# Bread.net
KiCad netlist of a schematic drawn in EAGLE
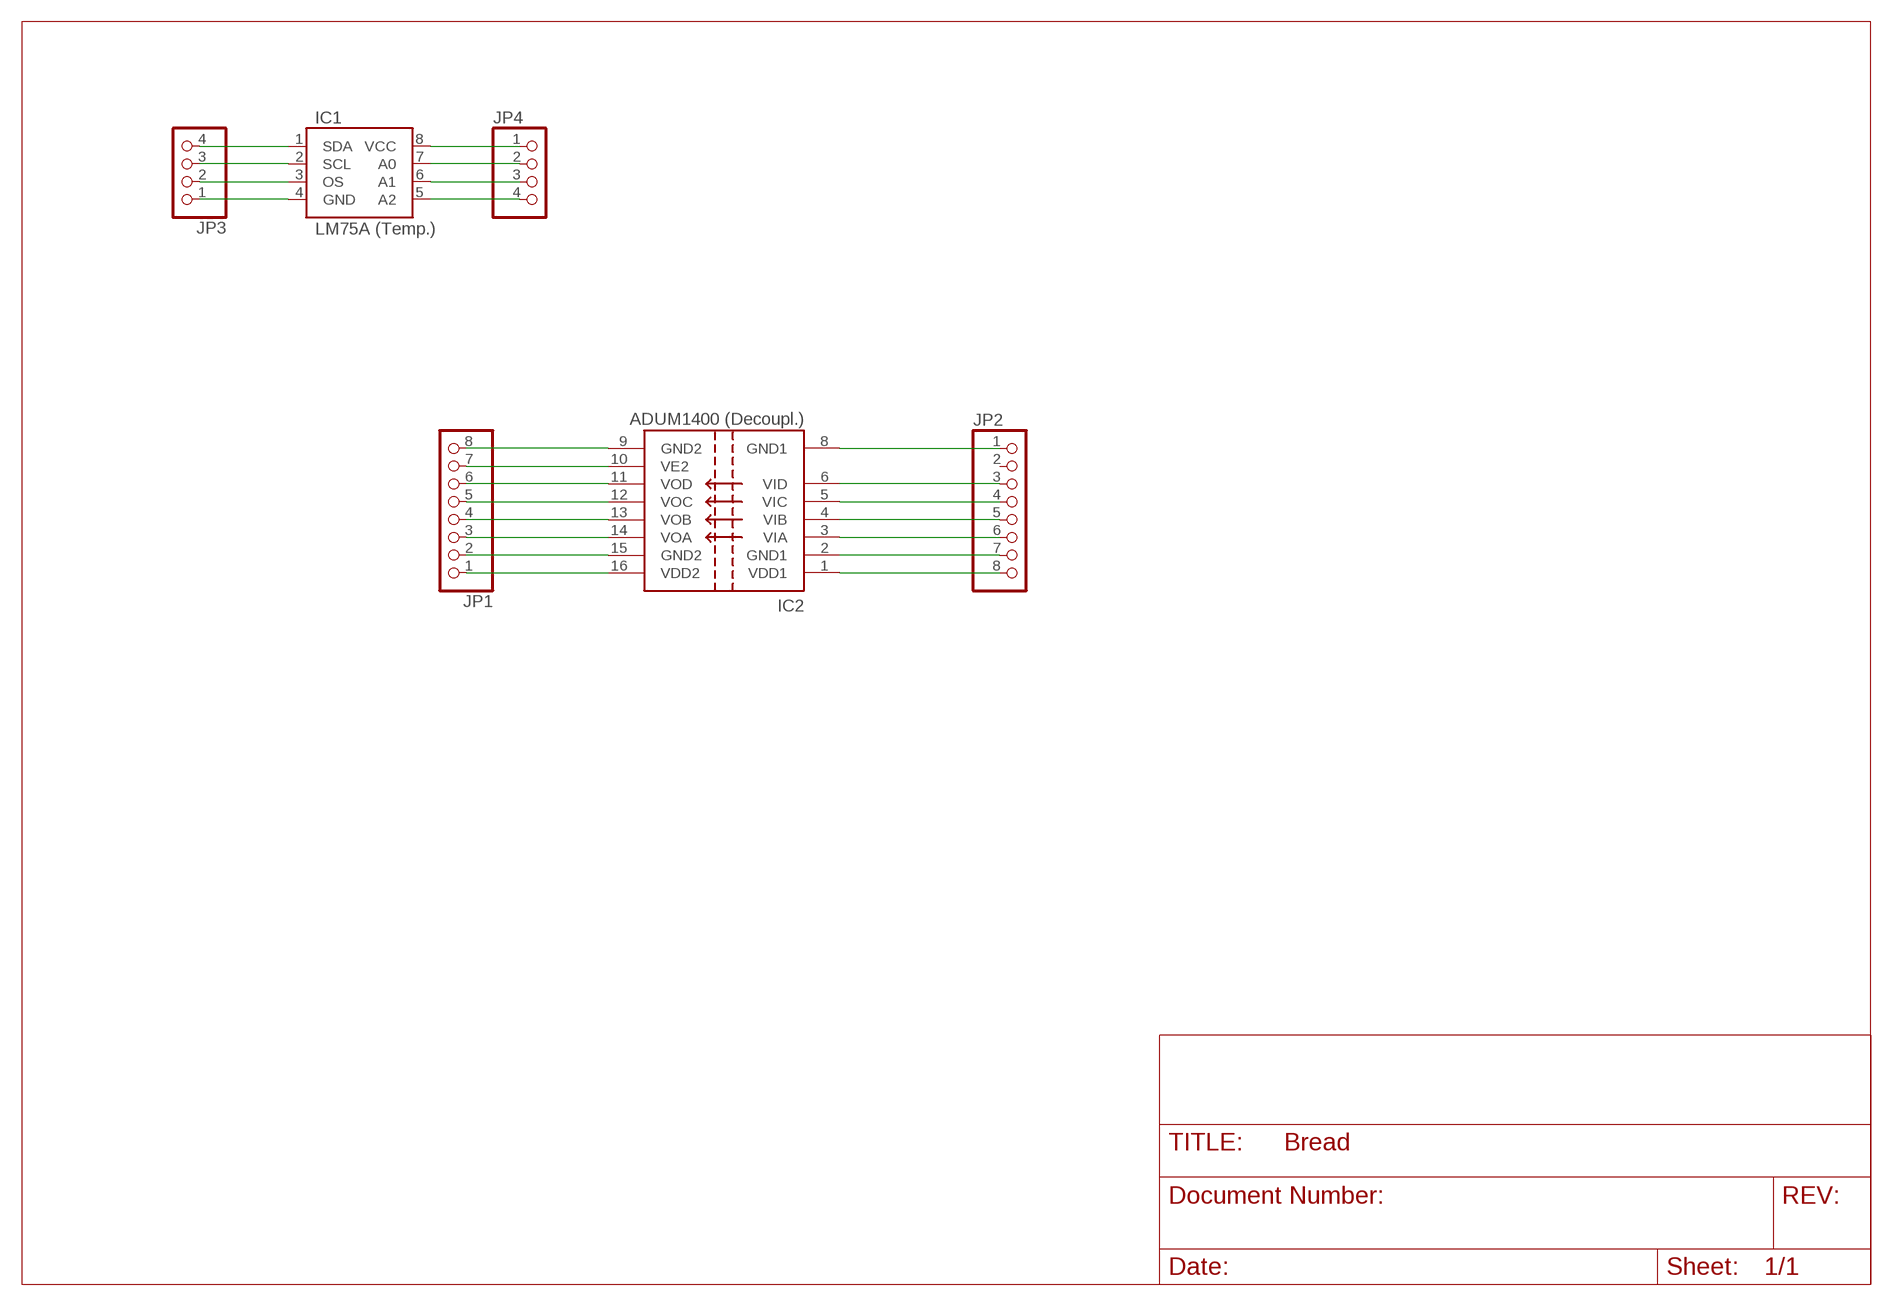
[diagram p0: schematic, sheet 1, part 1 of 2]
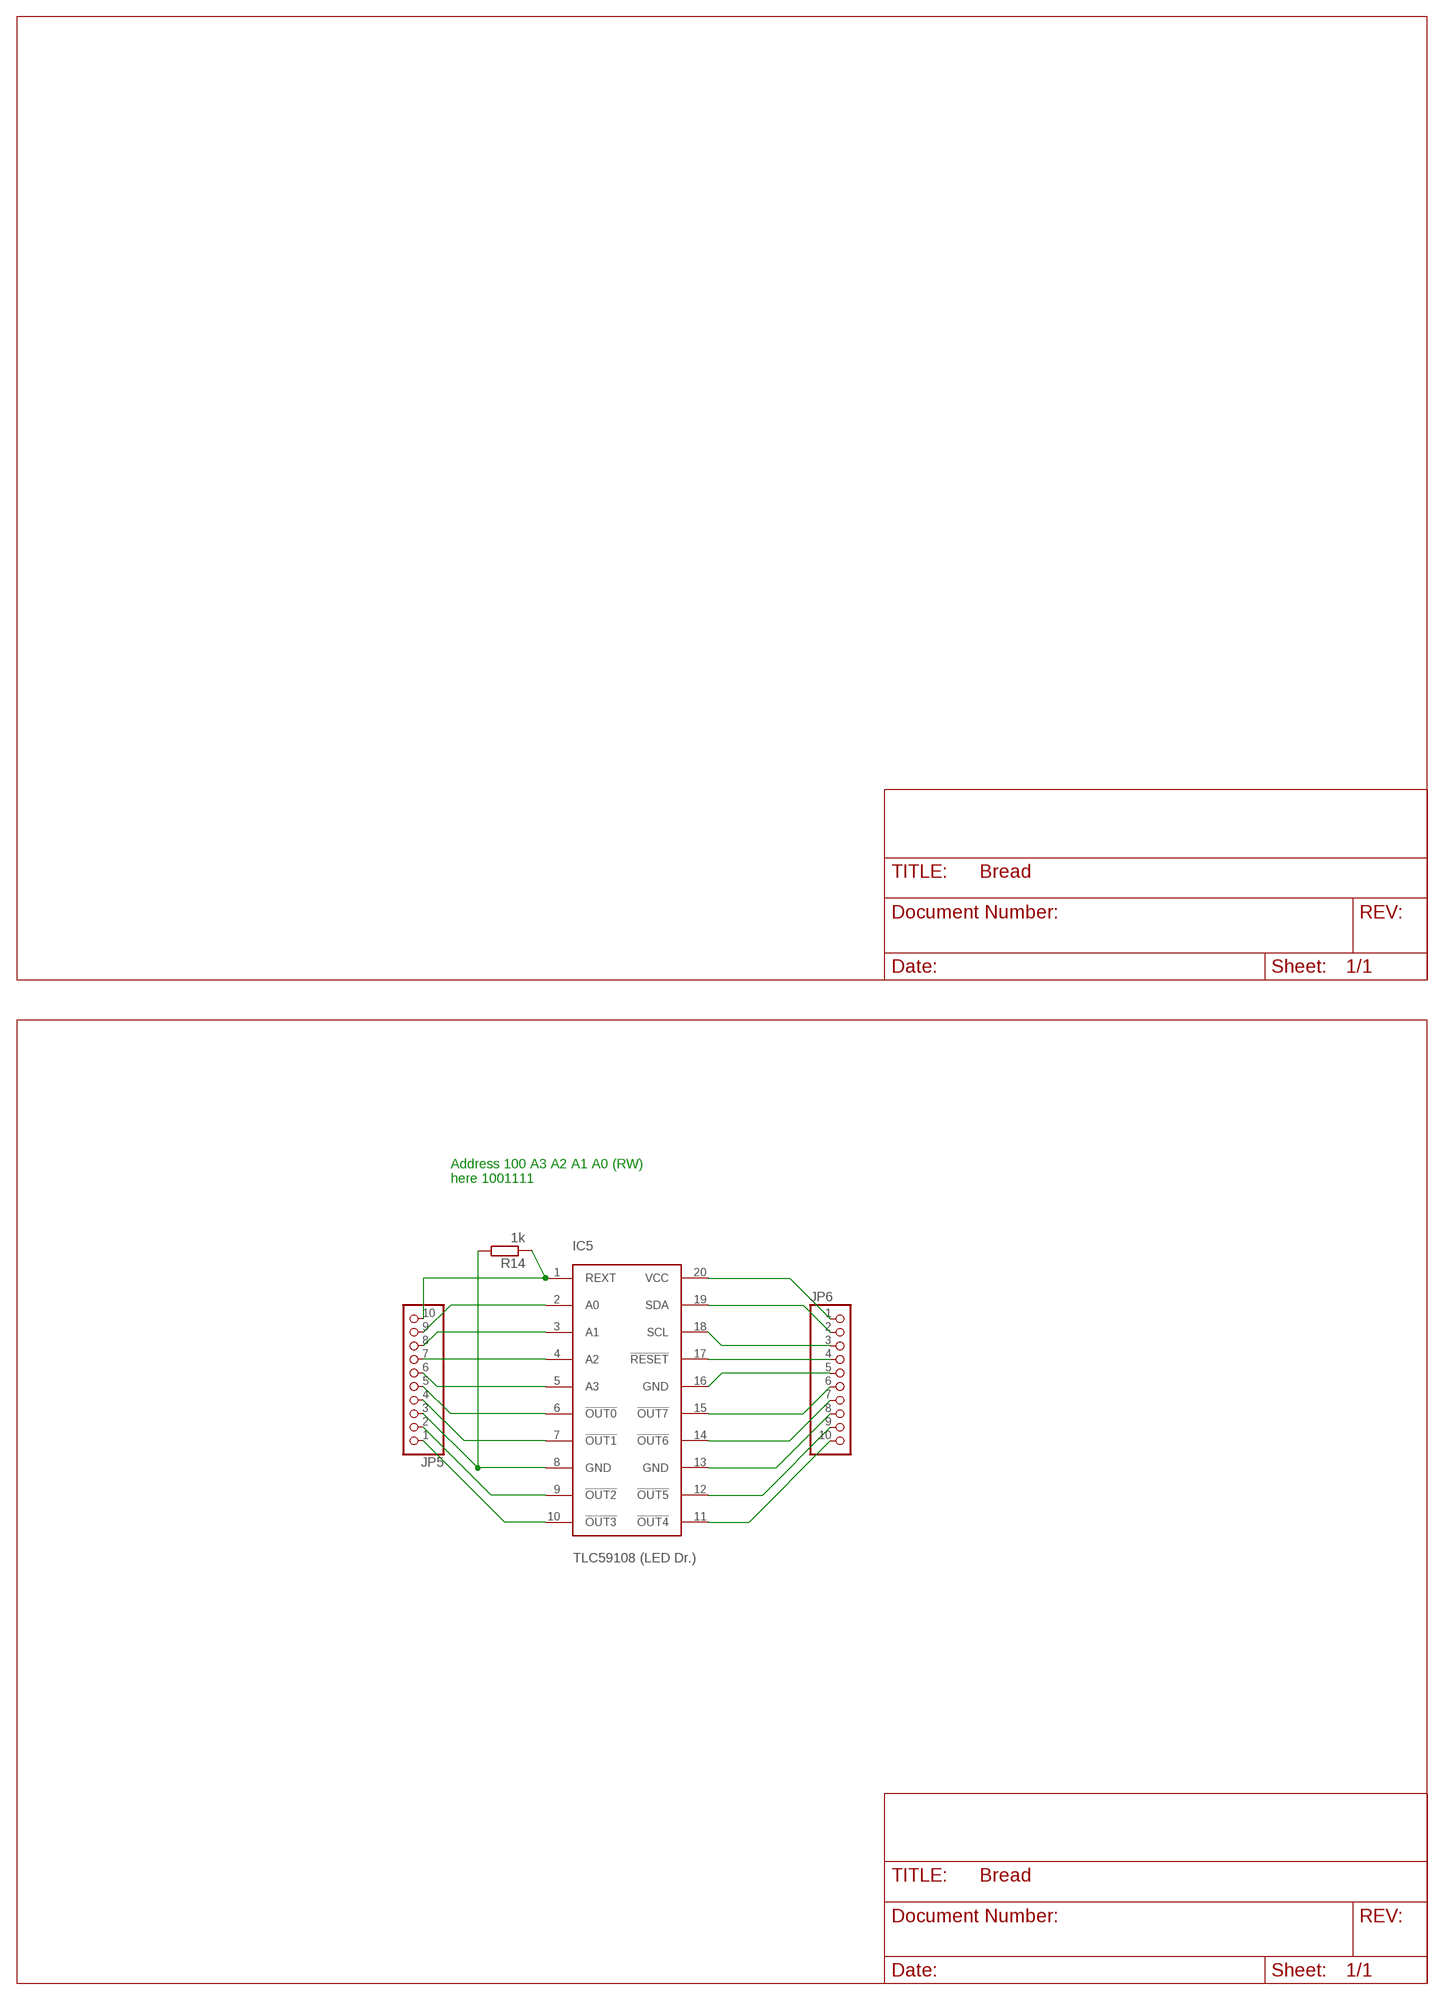
[diagram p1: schematic, sheet 1, part 2 of 2]

(export (version "E")
  (design (tool "Eeschema 10.0.6"))
  (components
    (comp (ref "IC1")
      (value "LM75A (Temp.)")
      (footprint "eagle-import:SO8")
      (libsource (lib "eagle-import") (part "LM75A"))
    )
    (comp (ref "IC2")
      (value "ADUM1400 (Decoupl.)")
      (footprint "eagle-import:SO16W")
      (libsource (lib "eagle-import") (part "ADUM1400"))
    )
    (comp (ref "IC5")
      (value "TLC59108 (LED Dr.)")
      (footprint "eagle-import:TSSOP20")
      (libsource (lib "eagle-import") (part "TLC59108"))
    )
    (comp (ref "JP1")
      (value "PINHD-1X8_2.54")
      (footprint "eagle-import:1X08")
      (libsource (lib "eagle-import") (part "PINHD-1X8_2.54"))
    )
    (comp (ref "JP2")
      (value "PINHD-1X8_2.54")
      (footprint "eagle-import:1X08")
      (libsource (lib "eagle-import") (part "PINHD-1X8_2.54"))
    )
    (comp (ref "JP3")
      (value "PINHD-1X4_2.54")
      (footprint "eagle-import:1X04")
      (libsource (lib "eagle-import") (part "PINHD-1X4_2.54"))
    )
    (comp (ref "JP4")
      (value "PINHD-1X4_2.54")
      (footprint "eagle-import:1X04")
      (libsource (lib "eagle-import") (part "PINHD-1X4_2.54"))
    )
    (comp (ref "JP5")
      (value "PINHD-1X10_2.54")
      (footprint "eagle-import:1X10")
      (libsource (lib "eagle-import") (part "PINHD-1X10_2.54"))
    )
    (comp (ref "JP6")
      (value "PINHD-1X10_2.54")
      (footprint "eagle-import:1X10")
      (libsource (lib "eagle-import") (part "PINHD-1X10_2.54"))
    )
    (comp (ref "R14")
      (value "1k")
      (footprint "eagle-import:R0603")
      (libsource (lib "eagle-import") (part "R-EU_R0603"))
    )
  )
  (nets
    (net (code "1") (name "Net-(IC1-A0)") (class "Default")
      (node (ref "IC1") (pin "7") (pinfunction "A0_7") (pintype "bidirectional"))
      (node (ref "JP4") (pin "2") (pinfunction "2_2") (pintype "passive"))
    )
    (net (code "2") (name "Net-(IC1-A1)") (class "Default")
      (node (ref "IC1") (pin "6") (pinfunction "A1_6") (pintype "bidirectional"))
      (node (ref "JP4") (pin "3") (pinfunction "3_3") (pintype "passive"))
    )
    (net (code "3") (name "Net-(IC1-A2)") (class "Default")
      (node (ref "IC1") (pin "5") (pinfunction "A2_5") (pintype "bidirectional"))
      (node (ref "JP4") (pin "4") (pinfunction "4_4") (pintype "passive"))
    )
    (net (code "4") (name "Net-(IC1-GND)") (class "Default")
      (node (ref "IC1") (pin "4") (pinfunction "GND_4") (pintype "bidirectional"))
      (node (ref "JP3") (pin "1") (pinfunction "1_1") (pintype "passive"))
    )
    (net (code "5") (name "Net-(IC1-OS)") (class "Default")
      (node (ref "IC1") (pin "3") (pinfunction "OS_3") (pintype "bidirectional"))
      (node (ref "JP3") (pin "2") (pinfunction "2_2") (pintype "passive"))
    )
    (net (code "6") (name "Net-(IC1-SCL)") (class "Default")
      (node (ref "IC1") (pin "2") (pinfunction "SCL_2") (pintype "bidirectional"))
      (node (ref "JP3") (pin "3") (pinfunction "3_3") (pintype "passive"))
    )
    (net (code "7") (name "Net-(IC1-SDA)") (class "Default")
      (node (ref "IC1") (pin "1") (pinfunction "SDA_1") (pintype "bidirectional"))
      (node (ref "JP3") (pin "4") (pinfunction "4_4") (pintype "passive"))
    )
    (net (code "8") (name "Net-(IC1-VCC)") (class "Default")
      (node (ref "IC1") (pin "8") (pinfunction "VCC_8") (pintype "bidirectional"))
      (node (ref "JP4") (pin "1") (pinfunction "1_1") (pintype "passive"))
    )
    (net (code "9") (name "Net-(IC2-GND1-Pad2)") (class "Default")
      (node (ref "IC2") (pin "2") (pinfunction "GND1_2") (pintype "power_in"))
      (node (ref "JP2") (pin "7") (pinfunction "7_7") (pintype "passive"))
    )
    (net (code "10") (name "Net-(IC2-GND1-Pad8)") (class "Default")
      (node (ref "IC2") (pin "8") (pinfunction "GND1_8") (pintype "power_in"))
      (node (ref "JP2") (pin "1") (pinfunction "1_1") (pintype "passive"))
    )
    (net (code "11") (name "Net-(IC2-GND2-Pad9)") (class "Default")
      (node (ref "IC2") (pin "9") (pinfunction "GND2_9") (pintype "power_in"))
      (node (ref "JP1") (pin "8") (pinfunction "8_8") (pintype "passive"))
    )
    (net (code "12") (name "Net-(IC2-GND2-Pad15)") (class "Default")
      (node (ref "IC2") (pin "15") (pinfunction "GND2_15") (pintype "power_in"))
      (node (ref "JP1") (pin "2") (pinfunction "2_2") (pintype "passive"))
    )
    (net (code "13") (name "Net-(IC2-VDD1)") (class "Default")
      (node (ref "IC2") (pin "1") (pinfunction "VDD1_1") (pintype "power_in"))
      (node (ref "JP2") (pin "8") (pinfunction "8_8") (pintype "passive"))
    )
    (net (code "14") (name "Net-(IC2-VDD2)") (class "Default")
      (node (ref "IC2") (pin "16") (pinfunction "VDD2_16") (pintype "power_in"))
      (node (ref "JP1") (pin "1") (pinfunction "1_1") (pintype "passive"))
    )
    (net (code "15") (name "Net-(IC2-VE2)") (class "Default")
      (node (ref "IC2") (pin "10") (pinfunction "VE2_10") (pintype "passive"))
      (node (ref "JP1") (pin "7") (pinfunction "7_7") (pintype "passive"))
    )
    (net (code "16") (name "Net-(IC2-VIA)") (class "Default")
      (node (ref "IC2") (pin "3") (pinfunction "VIA_3") (pintype "input"))
      (node (ref "JP2") (pin "6") (pinfunction "6_6") (pintype "passive"))
    )
    (net (code "17") (name "Net-(IC2-VIB)") (class "Default")
      (node (ref "IC2") (pin "4") (pinfunction "VIB_4") (pintype "input"))
      (node (ref "JP2") (pin "5") (pinfunction "5_5") (pintype "passive"))
    )
    (net (code "18") (name "Net-(IC2-VIC)") (class "Default")
      (node (ref "IC2") (pin "5") (pinfunction "VIC_5") (pintype "input"))
      (node (ref "JP2") (pin "4") (pinfunction "4_4") (pintype "passive"))
    )
    (net (code "19") (name "Net-(IC2-VID)") (class "Default")
      (node (ref "IC2") (pin "6") (pinfunction "VID_6") (pintype "input"))
      (node (ref "JP2") (pin "3") (pinfunction "3_3") (pintype "passive"))
    )
    (net (code "20") (name "Net-(IC2-VOA)") (class "Default")
      (node (ref "IC2") (pin "14") (pinfunction "VOA_14") (pintype "output"))
      (node (ref "JP1") (pin "3") (pinfunction "3_3") (pintype "passive"))
    )
    (net (code "21") (name "Net-(IC2-VOB)") (class "Default")
      (node (ref "IC2") (pin "13") (pinfunction "VOB_13") (pintype "output"))
      (node (ref "JP1") (pin "4") (pinfunction "4_4") (pintype "passive"))
    )
    (net (code "22") (name "Net-(IC2-VOC)") (class "Default")
      (node (ref "IC2") (pin "12") (pinfunction "VOC_12") (pintype "output"))
      (node (ref "JP1") (pin "5") (pinfunction "5_5") (pintype "passive"))
    )
    (net (code "23") (name "Net-(IC2-VOD)") (class "Default")
      (node (ref "IC2") (pin "11") (pinfunction "VOD_11") (pintype "output"))
      (node (ref "JP1") (pin "6") (pinfunction "6_6") (pintype "passive"))
    )
    (net (code "24") (name "Net-(IC5-A0)") (class "Default")
      (node (ref "IC5") (pin "2") (pinfunction "A0_2") (pintype "bidirectional"))
      (node (ref "JP5") (pin "9") (pinfunction "9_9") (pintype "passive"))
    )
    (net (code "25") (name "Net-(IC5-A1)") (class "Default")
      (node (ref "IC5") (pin "3") (pinfunction "A1_3") (pintype "bidirectional"))
      (node (ref "JP5") (pin "8") (pinfunction "8_8") (pintype "passive"))
    )
    (net (code "26") (name "Net-(IC5-A2)") (class "Default")
      (node (ref "IC5") (pin "4") (pinfunction "A2_4") (pintype "bidirectional"))
      (node (ref "JP5") (pin "7") (pinfunction "7_7") (pintype "passive"))
    )
    (net (code "27") (name "Net-(IC5-A3)") (class "Default")
      (node (ref "IC5") (pin "5") (pinfunction "A3_5") (pintype "bidirectional"))
      (node (ref "JP5") (pin "6") (pinfunction "6_6") (pintype "passive"))
    )
    (net (code "28") (name "Net-(IC5-GND-Pad8)") (class "Default")
      (node (ref "IC5") (pin "8") (pinfunction "GND_8") (pintype "bidirectional"))
      (node (ref "JP5") (pin "3") (pinfunction "3_3") (pintype "passive"))
      (node (ref "R14") (pin "2") (pinfunction "2_2") (pintype "passive"))
    )
    (net (code "29") (name "Net-(IC5-GND-Pad13)") (class "Default")
      (node (ref "IC5") (pin "13") (pinfunction "GND_13") (pintype "bidirectional"))
      (node (ref "JP6") (pin "8") (pinfunction "8_8") (pintype "passive"))
    )
    (net (code "30") (name "Net-(IC5-GND-Pad16)") (class "Default")
      (node (ref "IC5") (pin "16") (pinfunction "GND_16") (pintype "bidirectional"))
      (node (ref "JP6") (pin "5") (pinfunction "5_5") (pintype "passive"))
    )
    (net (code "31") (name "Net-(IC5-REXT)") (class "Default")
      (node (ref "IC5") (pin "1") (pinfunction "REXT_1") (pintype "bidirectional"))
      (node (ref "JP5") (pin "10") (pinfunction "10_10") (pintype "passive"))
      (node (ref "R14") (pin "1") (pinfunction "1_1") (pintype "passive"))
    )
    (net (code "32") (name "Net-(IC5-SCL)") (class "Default")
      (node (ref "IC5") (pin "18") (pinfunction "SCL_18") (pintype "bidirectional"))
      (node (ref "JP6") (pin "3") (pinfunction "3_3") (pintype "passive"))
    )
    (net (code "33") (name "Net-(IC5-SDA)") (class "Default")
      (node (ref "IC5") (pin "19") (pinfunction "SDA_19") (pintype "bidirectional"))
      (node (ref "JP6") (pin "2") (pinfunction "2_2") (pintype "passive"))
    )
    (net (code "34") (name "Net-(IC5-VCC)") (class "Default")
      (node (ref "IC5") (pin "20") (pinfunction "VCC_20") (pintype "bidirectional"))
      (node (ref "JP6") (pin "1") (pinfunction "1_1") (pintype "passive"))
    )
    (net (code "35") (name "Net-(IC5-~{OUT0})") (class "Default")
      (node (ref "IC5") (pin "6") (pinfunction "~{OUT0}_6") (pintype "bidirectional"))
      (node (ref "JP5") (pin "5") (pinfunction "5_5") (pintype "passive"))
    )
    (net (code "36") (name "Net-(IC5-~{OUT1})") (class "Default")
      (node (ref "IC5") (pin "7") (pinfunction "~{OUT1}_7") (pintype "bidirectional"))
      (node (ref "JP5") (pin "4") (pinfunction "4_4") (pintype "passive"))
    )
    (net (code "37") (name "Net-(IC5-~{OUT2})") (class "Default")
      (node (ref "IC5") (pin "9") (pinfunction "~{OUT2}_9") (pintype "bidirectional"))
      (node (ref "JP5") (pin "2") (pinfunction "2_2") (pintype "passive"))
    )
    (net (code "38") (name "Net-(IC5-~{OUT3})") (class "Default")
      (node (ref "IC5") (pin "10") (pinfunction "~{OUT3}_10") (pintype "bidirectional"))
      (node (ref "JP5") (pin "1") (pinfunction "1_1") (pintype "passive"))
    )
    (net (code "39") (name "Net-(IC5-~{OUT4})") (class "Default")
      (node (ref "IC5") (pin "11") (pinfunction "~{OUT4}_11") (pintype "bidirectional"))
      (node (ref "JP6") (pin "10") (pinfunction "10_10") (pintype "passive"))
    )
    (net (code "40") (name "Net-(IC5-~{OUT5})") (class "Default")
      (node (ref "IC5") (pin "12") (pinfunction "~{OUT5}_12") (pintype "bidirectional"))
      (node (ref "JP6") (pin "9") (pinfunction "9_9") (pintype "passive"))
    )
    (net (code "41") (name "Net-(IC5-~{OUT6})") (class "Default")
      (node (ref "IC5") (pin "14") (pinfunction "~{OUT6}_14") (pintype "bidirectional"))
      (node (ref "JP6") (pin "7") (pinfunction "7_7") (pintype "passive"))
    )
    (net (code "42") (name "Net-(IC5-~{OUT7})") (class "Default")
      (node (ref "IC5") (pin "15") (pinfunction "~{OUT7}_15") (pintype "bidirectional"))
      (node (ref "JP6") (pin "6") (pinfunction "6_6") (pintype "passive"))
    )
    (net (code "43") (name "Net-(IC5-~{RESET})") (class "Default")
      (node (ref "IC5") (pin "17") (pinfunction "~{RESET}_17") (pintype "bidirectional"))
      (node (ref "JP6") (pin "4") (pinfunction "4_4") (pintype "passive"))
    )
    (net (code "44") (name "unconnected-(JP2-Pad2)") (class "Default")
      (node (ref "JP2") (pin "2") (pinfunction "2_2") (pintype "passive"))
    )
  )
)
